# Sheet1.net
KiCad netlist of a schematic drawn in Altium Designer
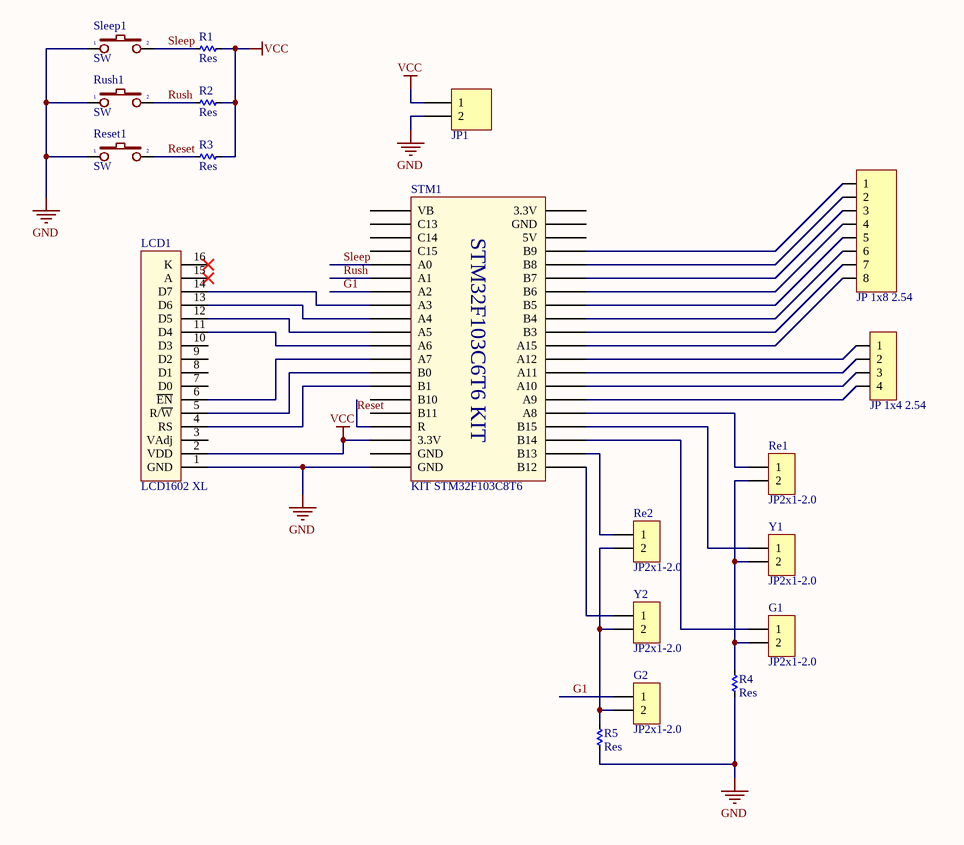
[diagram p0: Sheet1.SchDoc]

(export (version "E")
  (design (tool "Eeschema 10.0.6"))
  (components
    (comp (ref "Control7Seg")
      (value "JP 1x4 2.54")
      (footprint "JP 1x4 DT")
      (description "Cắm")
      (libsource (lib "Altium_Lib_by_KhueNguyenCreator") (part "JP 1x4 2.54 Duc Thang"))
    )
    (comp (ref "G1")
      (value "JP2x1-2.0")
      (footprint "J2-C1T")
      (description "WR-PHD 2.00 mm Socket Header")
      (fields
        (field (name "MANUFACTURER") "Würth Elektronik eiSos GmbH")
        (field (name "PARTNO") "62000211821")
        (field (name "CREATED BY") "Karrer Zheng")
      )
      (libsource (lib "thu vien 3d") (part "JP2x1-2.0"))
    )
    (comp (ref "G2")
      (value "JP2x1-2.0")
      (footprint "J2-C1T")
      (description "WR-PHD 2.00 mm Socket Header")
      (fields
        (field (name "MANUFACTURER") "Würth Elektronik eiSos GmbH")
        (field (name "PARTNO") "62000211821")
        (field (name "CREATED BY") "Karrer Zheng")
      )
      (libsource (lib "thu vien 3d") (part "JP2x1-2.0"))
    )
    (comp (ref "JP1")
      (value "Header 2_1")
      (footprint "HED2")
      (description "Header, 2-Pin")
      (fields (field (name "MANUFACTURER") "Generic Components"))
      (libsource (lib "syhaunguyen") (part "Header 2_1"))
    )
    (comp (ref "LCD1")
      (value "LCD1602 XL")
      (footprint "LCD1602")
      (description "LCD 1602 Xanh Lá")
      (libsource (lib "Altium_Lib_by_KhueNguyenCreator") (part "LCD1602 XL"))
    )
    (comp (ref "Led_pin")
      (value "JP 1x8 2.54")
      (footprint "JP 1x8 DT")
      (description "Cắm")
      (libsource (lib "Altium_Lib_by_KhueNguyenCreator") (part "JP 1x8 2.54 Duc Thang"))
    )
    (comp (ref "R1")
      (value "Res")
      (footprint "RES-1/2W")
      (fields
        (field (name "MANUFACTURER") "Generic Components")
        (field (name "PUBLISHER") "Altium Hobart Technology Centre")
      )
      (libsource (lib "thu vien 3d") (part "Res"))
    )
    (comp (ref "R2")
      (value "Res")
      (footprint "RES-1/2W")
      (fields
        (field (name "MANUFACTURER") "Generic Components")
        (field (name "PUBLISHER") "Altium Hobart Technology Centre")
      )
      (libsource (lib "thu vien 3d") (part "Res"))
    )
    (comp (ref "R3")
      (value "Res")
      (footprint "RES-1/2W")
      (fields
        (field (name "MANUFACTURER") "Generic Components")
        (field (name "PUBLISHER") "Altium Hobart Technology Centre")
      )
      (libsource (lib "thu vien 3d") (part "Res"))
    )
    (comp (ref "R4")
      (value "Res")
      (footprint "RES-1/2W")
      (fields
        (field (name "MANUFACTURER") "Generic Components")
        (field (name "PUBLISHER") "Altium Hobart Technology Centre")
      )
      (libsource (lib "thu vien 3d") (part "Res"))
    )
    (comp (ref "R5")
      (value "Res")
      (footprint "RES-1/2W")
      (fields
        (field (name "MANUFACTURER") "Generic Components")
        (field (name "PUBLISHER") "Altium Hobart Technology Centre")
      )
      (libsource (lib "thu vien 3d") (part "Res"))
    )
    (comp (ref "Re1")
      (value "JP2x1-2.0")
      (footprint "J2-C1T")
      (description "WR-PHD 2.00 mm Socket Header")
      (fields
        (field (name "MANUFACTURER") "Würth Elektronik eiSos GmbH")
        (field (name "PARTNO") "62000211821")
        (field (name "CREATED BY") "Karrer Zheng")
      )
      (libsource (lib "thu vien 3d") (part "JP2x1-2.0"))
    )
    (comp (ref "Re2")
      (value "JP2x1-2.0")
      (footprint "J2-C1T")
      (description "WR-PHD 2.00 mm Socket Header")
      (fields
        (field (name "MANUFACTURER") "Würth Elektronik eiSos GmbH")
        (field (name "PARTNO") "62000211821")
        (field (name "CREATED BY") "Karrer Zheng")
      )
      (libsource (lib "thu vien 3d") (part "JP2x1-2.0"))
    )
    (comp (ref "Reset1")
      (value "SW")
      (footprint "SW2")
      (description "Switch button 2 pin")
      (libsource (lib "syhaunguyen") (part "SW2"))
    )
    (comp (ref "Rush1")
      (value "SW")
      (footprint "SW2")
      (description "Switch button 2 pin")
      (libsource (lib "syhaunguyen") (part "SW2"))
    )
    (comp (ref "Sleep1")
      (value "SW")
      (footprint "SW2")
      (description "Switch button 2 pin")
      (libsource (lib "syhaunguyen") (part "SW2"))
    )
    (comp (ref "STM1")
      (value "KIT STM32F103C8T6")
      (footprint "STM32F103 KIT")
      (description "KIT STM32F103C8T6 Bluepill")
      (libsource (lib "Altium_Lib_by_KhueNguyenCreator") (part "STM32f103 Bluepill"))
    )
    (comp (ref "Y1")
      (value "JP2x1-2.0")
      (footprint "J2-C1T")
      (description "WR-PHD 2.00 mm Socket Header")
      (fields
        (field (name "MANUFACTURER") "Würth Elektronik eiSos GmbH")
        (field (name "PARTNO") "62000211821")
        (field (name "CREATED BY") "Karrer Zheng")
      )
      (libsource (lib "thu vien 3d") (part "JP2x1-2.0"))
    )
    (comp (ref "Y2")
      (value "JP2x1-2.0")
      (footprint "J2-C1T")
      (description "WR-PHD 2.00 mm Socket Header")
      (fields
        (field (name "MANUFACTURER") "Würth Elektronik eiSos GmbH")
        (field (name "PARTNO") "62000211821")
        (field (name "CREATED BY") "Karrer Zheng")
      )
      (libsource (lib "thu vien 3d") (part "JP2x1-2.0"))
    )
  )
  (nets
    (net (code "1") (name "/G1") (class "Default")
      (node (ref "G2") (pin "1") (pinfunction "1_1") (pintype "passive"))
      (node (ref "STM1") (pin "27") (pinfunction "A2_27") (pintype "passive"))
    )
    (net (code "2") (name "/Reset") (class "Default")
      (node (ref "R3") (pin "2") (pinfunction "2_2") (pintype "passive"))
      (node (ref "Reset1") (pin "2") (pinfunction "2_2") (pintype "passive"))
      (node (ref "STM1") (pin "37") (pinfunction "R_37") (pintype "passive"))
    )
    (net (code "3") (name "/Rush") (class "Default")
      (node (ref "R2") (pin "2") (pinfunction "2_2") (pintype "passive"))
      (node (ref "Rush1") (pin "2") (pinfunction "2_2") (pintype "passive"))
      (node (ref "STM1") (pin "26") (pinfunction "A1_26") (pintype "passive"))
    )
    (net (code "4") (name "/Sleep") (class "Default")
      (node (ref "R1") (pin "2") (pinfunction "2_2") (pintype "passive"))
      (node (ref "STM1") (pin "25") (pinfunction "A0_25") (pintype "passive"))
      (node (ref "Sleep1") (pin "2") (pinfunction "2_2") (pintype "passive"))
    )
    (net (code "5") (name "GND") (class "Default")
      (node (ref "JP1") (pin "2") (pinfunction "2_2") (pintype "passive"))
      (node (ref "LCD1") (pin "1") (pinfunction "GND_1") (pintype "passive"))
      (node (ref "R4") (pin "2") (pinfunction "2_2") (pintype "passive"))
      (node (ref "R5") (pin "2") (pinfunction "2_2") (pintype "passive"))
      (node (ref "Reset1") (pin "1") (pinfunction "1_1") (pintype "passive"))
      (node (ref "Rush1") (pin "1") (pinfunction "1_1") (pintype "passive"))
      (node (ref "STM1") (pin "40") (pinfunction "GND_40") (pintype "passive"))
      (node (ref "Sleep1") (pin "1") (pinfunction "1_1") (pintype "passive"))
    )
    (net (code "6") (name "Net-(G1-Pad2)") (class "Default")
      (node (ref "G1") (pin "2") (pinfunction "2_2") (pintype "passive"))
      (node (ref "R4") (pin "1") (pinfunction "1_1") (pintype "passive"))
      (node (ref "Re1") (pin "2") (pinfunction "2_2") (pintype "passive"))
      (node (ref "Y1") (pin "2") (pinfunction "2_2") (pintype "passive"))
    )
    (net (code "7") (name "Net-(G2-Pad2)") (class "Default")
      (node (ref "G2") (pin "2") (pinfunction "2_2") (pintype "passive"))
      (node (ref "R5") (pin "1") (pinfunction "1_1") (pintype "passive"))
      (node (ref "Re2") (pin "2") (pinfunction "2_2") (pintype "passive"))
      (node (ref "Y2") (pin "2") (pinfunction "2_2") (pintype "passive"))
    )
    (net (code "8") (name "Net-(LCD1-D4)") (class "Default")
      (node (ref "LCD1") (pin "11") (pinfunction "D4_11") (pintype "passive"))
      (node (ref "STM1") (pin "31") (pinfunction "A6_31") (pintype "passive"))
    )
    (net (code "9") (name "Net-(LCD1-D5)") (class "Default")
      (node (ref "LCD1") (pin "12") (pinfunction "D5_12") (pintype "passive"))
      (node (ref "STM1") (pin "30") (pinfunction "A5_30") (pintype "passive"))
    )
    (net (code "10") (name "Net-(LCD1-D6)") (class "Default")
      (node (ref "LCD1") (pin "13") (pinfunction "D6_13") (pintype "passive"))
      (node (ref "STM1") (pin "29") (pinfunction "A4_29") (pintype "passive"))
    )
    (net (code "11") (name "Net-(LCD1-D7)") (class "Default")
      (node (ref "LCD1") (pin "14") (pinfunction "D7_14") (pintype "passive"))
      (node (ref "STM1") (pin "28") (pinfunction "A3_28") (pintype "passive"))
    )
    (net (code "12") (name "Net-(LCD1-RS)") (class "Default")
      (node (ref "LCD1") (pin "4") (pinfunction "RS_4") (pintype "passive"))
      (node (ref "STM1") (pin "34") (pinfunction "B1_34") (pintype "passive"))
    )
    (net (code "13") (name "Net-(LCD1-R{slash}~{W})") (class "Default")
      (node (ref "LCD1") (pin "5") (pinfunction "R/~{W}_5") (pintype "passive"))
      (node (ref "STM1") (pin "33") (pinfunction "B0_33") (pintype "passive"))
    )
    (net (code "14") (name "Net-(LCD1-~{EN})") (class "Default")
      (node (ref "LCD1") (pin "6") (pinfunction "~{EN}_6") (pintype "passive"))
      (node (ref "STM1") (pin "32") (pinfunction "A7_32") (pintype "passive"))
    )
    (net (code "15") (name "Net-(STM1-A8)") (class "Default")
      (node (ref "Re1") (pin "1") (pinfunction "1_1") (pintype "passive"))
      (node (ref "STM1") (pin "5") (pinfunction "A8_5") (pintype "passive"))
    )
    (net (code "16") (name "Net-(STM1-A9)") (class "Default")
      (node (ref "Control7Seg") (pin "4") (pinfunction "4_4") (pintype "passive"))
      (node (ref "STM1") (pin "6") (pinfunction "A9_6") (pintype "passive"))
    )
    (net (code "17") (name "Net-(STM1-A10)") (class "Default")
      (node (ref "Control7Seg") (pin "3") (pinfunction "3_3") (pintype "passive"))
      (node (ref "STM1") (pin "7") (pinfunction "A10_7") (pintype "passive"))
    )
    (net (code "18") (name "Net-(STM1-A11)") (class "Default")
      (node (ref "Control7Seg") (pin "2") (pinfunction "2_2") (pintype "passive"))
      (node (ref "STM1") (pin "8") (pinfunction "A11_8") (pintype "passive"))
    )
    (net (code "19") (name "Net-(STM1-A12)") (class "Default")
      (node (ref "Control7Seg") (pin "1") (pinfunction "1_1") (pintype "passive"))
      (node (ref "STM1") (pin "9") (pinfunction "A12_9") (pintype "passive"))
    )
    (net (code "20") (name "Net-(STM1-A15)") (class "Default")
      (node (ref "Led_pin") (pin "8") (pinfunction "8_8") (pintype "passive"))
      (node (ref "STM1") (pin "10") (pinfunction "A15_10") (pintype "passive"))
    )
    (net (code "21") (name "Net-(STM1-B3)") (class "Default")
      (node (ref "Led_pin") (pin "7") (pinfunction "7_7") (pintype "passive"))
      (node (ref "STM1") (pin "11") (pinfunction "B3_11") (pintype "passive"))
    )
    (net (code "22") (name "Net-(STM1-B4)") (class "Default")
      (node (ref "Led_pin") (pin "6") (pinfunction "6_6") (pintype "passive"))
      (node (ref "STM1") (pin "12") (pinfunction "B4_12") (pintype "passive"))
    )
    (net (code "23") (name "Net-(STM1-B5)") (class "Default")
      (node (ref "Led_pin") (pin "5") (pinfunction "5_5") (pintype "passive"))
      (node (ref "STM1") (pin "13") (pinfunction "B5_13") (pintype "passive"))
    )
    (net (code "24") (name "Net-(STM1-B6)") (class "Default")
      (node (ref "Led_pin") (pin "4") (pinfunction "4_4") (pintype "passive"))
      (node (ref "STM1") (pin "14") (pinfunction "B6_14") (pintype "passive"))
    )
    (net (code "25") (name "Net-(STM1-B7)") (class "Default")
      (node (ref "Led_pin") (pin "3") (pinfunction "3_3") (pintype "passive"))
      (node (ref "STM1") (pin "15") (pinfunction "B7_15") (pintype "passive"))
    )
    (net (code "26") (name "Net-(STM1-B8)") (class "Default")
      (node (ref "Led_pin") (pin "2") (pinfunction "2_2") (pintype "passive"))
      (node (ref "STM1") (pin "16") (pinfunction "B8_16") (pintype "passive"))
    )
    (net (code "27") (name "Net-(STM1-B9)") (class "Default")
      (node (ref "Led_pin") (pin "1") (pinfunction "1_1") (pintype "passive"))
      (node (ref "STM1") (pin "17") (pinfunction "B9_17") (pintype "passive"))
    )
    (net (code "28") (name "Net-(STM1-B12)") (class "Default")
      (node (ref "STM1") (pin "1") (pinfunction "B12_1") (pintype "passive"))
      (node (ref "Y2") (pin "1") (pinfunction "1_1") (pintype "passive"))
    )
    (net (code "29") (name "Net-(STM1-B13)") (class "Default")
      (node (ref "Re2") (pin "1") (pinfunction "1_1") (pintype "passive"))
      (node (ref "STM1") (pin "2") (pinfunction "B13_2") (pintype "passive"))
    )
    (net (code "30") (name "Net-(STM1-B14)") (class "Default")
      (node (ref "G1") (pin "1") (pinfunction "1_1") (pintype "passive"))
      (node (ref "STM1") (pin "3") (pinfunction "B14_3") (pintype "passive"))
    )
    (net (code "31") (name "Net-(STM1-B15)") (class "Default")
      (node (ref "STM1") (pin "4") (pinfunction "B15_4") (pintype "passive"))
      (node (ref "Y1") (pin "1") (pinfunction "1_1") (pintype "passive"))
    )
    (net (code "32") (name "VCC") (class "Default")
      (node (ref "JP1") (pin "1") (pinfunction "1_1") (pintype "passive"))
      (node (ref "LCD1") (pin "2") (pinfunction "VDD_2") (pintype "passive"))
      (node (ref "R1") (pin "1") (pinfunction "1_1") (pintype "passive"))
      (node (ref "R2") (pin "1") (pinfunction "1_1") (pintype "passive"))
      (node (ref "R3") (pin "1") (pinfunction "1_1") (pintype "passive"))
      (node (ref "STM1") (pin "38") (pinfunction "3.3V_38") (pintype "passive"))
    )
    (net (code "33") (name "unconnected-(LCD1-A-Pad15)") (class "Default")
      (node (ref "LCD1") (pin "15") (pinfunction "A_15") (pintype "passive+no_connect"))
    )
    (net (code "34") (name "unconnected-(LCD1-D0-Pad7)") (class "Default")
      (node (ref "LCD1") (pin "7") (pinfunction "D0_7") (pintype "passive"))
    )
    (net (code "35") (name "unconnected-(LCD1-D1-Pad8)") (class "Default")
      (node (ref "LCD1") (pin "8") (pinfunction "D1_8") (pintype "passive"))
    )
    (net (code "36") (name "unconnected-(LCD1-D2-Pad9)") (class "Default")
      (node (ref "LCD1") (pin "9") (pinfunction "D2_9") (pintype "passive"))
    )
    (net (code "37") (name "unconnected-(LCD1-D3-Pad10)") (class "Default")
      (node (ref "LCD1") (pin "10") (pinfunction "D3_10") (pintype "passive"))
    )
    (net (code "38") (name "unconnected-(LCD1-K-Pad16)") (class "Default")
      (node (ref "LCD1") (pin "16") (pinfunction "K_16") (pintype "passive+no_connect"))
    )
    (net (code "39") (name "unconnected-(LCD1-VAdj-Pad3)") (class "Default")
      (node (ref "LCD1") (pin "3") (pinfunction "VAdj_3") (pintype "passive"))
    )
    (net (code "40") (name "unconnected-(STM1-3.3V-Pad20)") (class "Default")
      (node (ref "STM1") (pin "20") (pinfunction "3.3V_20") (pintype "passive"))
    )
    (net (code "41") (name "unconnected-(STM1-5V-Pad18)") (class "Default")
      (node (ref "STM1") (pin "18") (pinfunction "5V_18") (pintype "passive"))
    )
    (net (code "42") (name "unconnected-(STM1-B10-Pad35)") (class "Default")
      (node (ref "STM1") (pin "35") (pinfunction "B10_35") (pintype "passive"))
    )
    (net (code "43") (name "unconnected-(STM1-B11-Pad36)") (class "Default")
      (node (ref "STM1") (pin "36") (pinfunction "B11_36") (pintype "passive"))
    )
    (net (code "44") (name "unconnected-(STM1-C13-Pad22)") (class "Default")
      (node (ref "STM1") (pin "22") (pinfunction "C13_22") (pintype "passive"))
    )
    (net (code "45") (name "unconnected-(STM1-C14-Pad23)") (class "Default")
      (node (ref "STM1") (pin "23") (pinfunction "C14_23") (pintype "passive"))
    )
    (net (code "46") (name "unconnected-(STM1-C15-Pad24)") (class "Default")
      (node (ref "STM1") (pin "24") (pinfunction "C15_24") (pintype "passive"))
    )
    (net (code "47") (name "unconnected-(STM1-GND-Pad19)") (class "Default")
      (node (ref "STM1") (pin "19") (pinfunction "GND_19") (pintype "passive"))
    )
    (net (code "48") (name "unconnected-(STM1-GND-Pad39)") (class "Default")
      (node (ref "STM1") (pin "39") (pinfunction "GND_39") (pintype "passive"))
    )
    (net (code "49") (name "unconnected-(STM1-VB-Pad21)") (class "Default")
      (node (ref "STM1") (pin "21") (pinfunction "VB_21") (pintype "passive"))
    )
  )
)
